# DC-Motor-DRV.net
KiCad netlist of a schematic drawn in Altium Designer
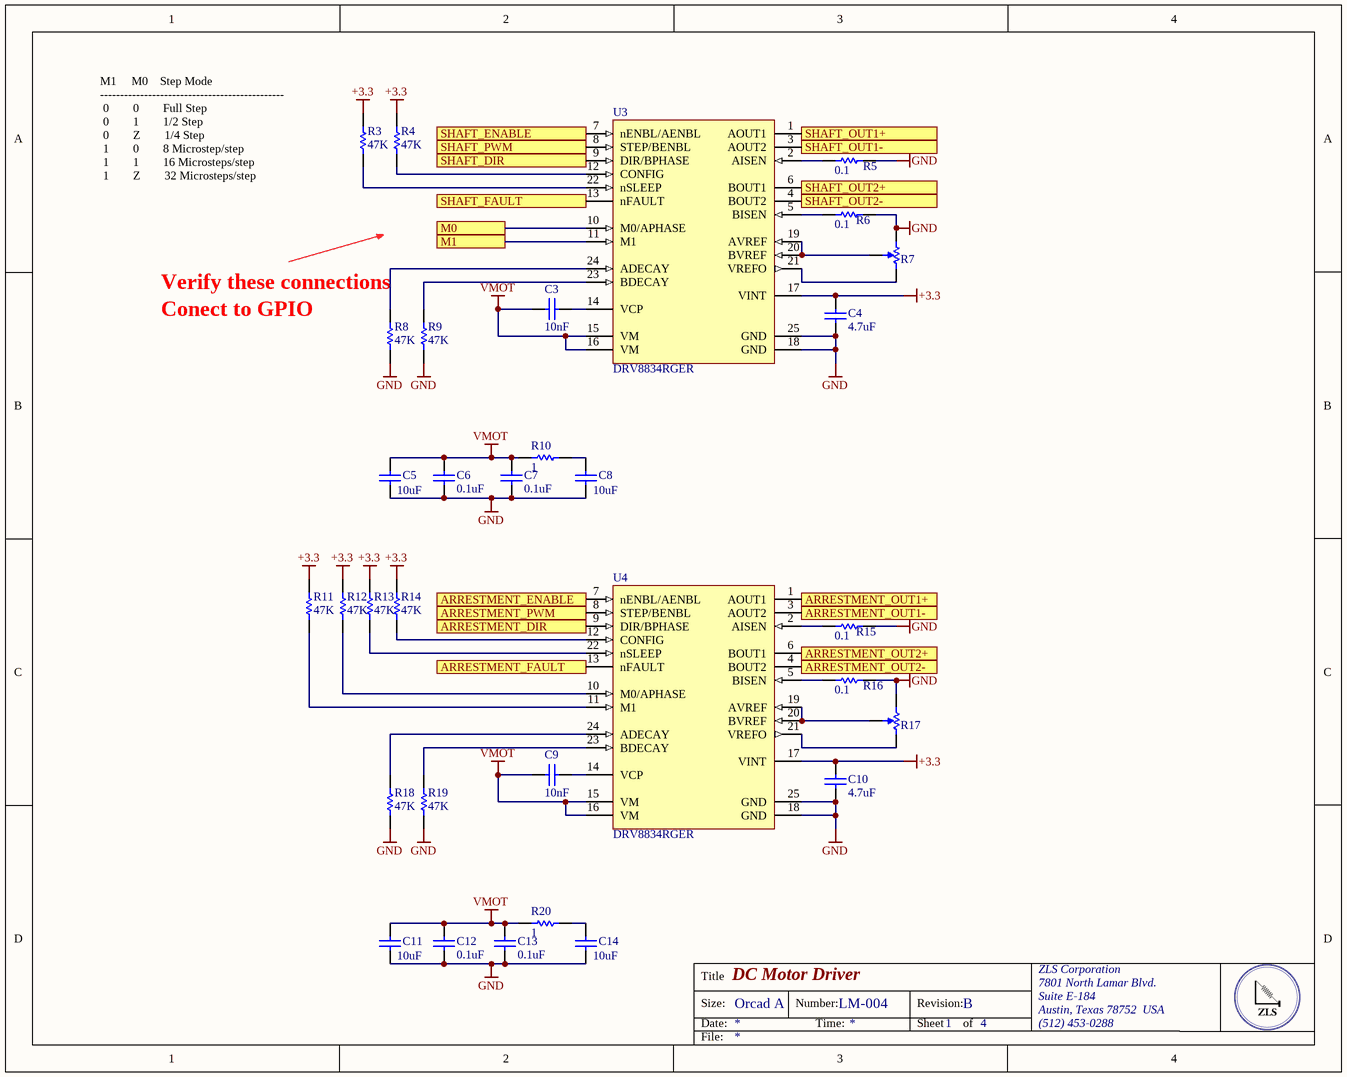
[diagram p0: DC-Motor-DRV.SchDoc]

(export (version "E")
  (design (tool "Eeschema 10.0.6"))
  (components
    (comp (ref "C3")
      (value "10nF")
      (footprint "CAPC0603(1608)100_L")
      (description "CAP 10nF 16V ±20% 0603 (1608 Metric) Thickness 1mm SMD")
      (fields (field (name "TOLERANCE") "Â±20%") (field (name "MANUFACTURER") "Kyocera AVX"))
      (libsource (lib "Altium Content Vault") (part "CAP"))
    )
    (comp (ref "C4")
      (value "4.7uF")
      (footprint "CAPC0603(1608)55_M")
      (description "CAP 4.7uF 6.3V ±10% 0603 (1608 Metric) Thickness 0.55mm SMD")
      (fields (field (name "TOLERANCE") "Â±10%") (field (name "MANUFACTURER") "KEMET"))
      (libsource (lib "Altium Content Vault") (part "CAP"))
    )
    (comp (ref "C5")
      (value "10uF")
      (footprint "CAPC0805(2012)145_N")
      (description "CAP CER 0.1UF 25V X7R 0805")
      (fields
        (field (name "MANUFACTURER") "Murata Electronics North America")
        (field (name "MANUFACTURER PART NUMBER") "GRM21BR71E104KA01L")
      )
      (libsource (lib "Altium Content Vault") (part "CMP-1036-04795-1"))
    )
    (comp (ref "C6")
      (value "0.1uF")
      (footprint "CAPC1608X94X35LL15T15")
      (description "CAP .1UF 16V CERAMIC X7R 0603")
      (fields
        (field (name "MANUFACTURER") "Yageo")
        (field (name "MANUFACTURER PART NUMBER") "CC0603KRX7R7BB105")
      )
      (libsource (lib "Altium Content Vault") (part "CAP-NP-2"))
    )
    (comp (ref "C7")
      (value "0.1uF")
      (footprint "CAPC1608X94X35LL15T15")
      (description "CAP .1UF 16V CERAMIC X7R 0603")
      (fields
        (field (name "MANUFACTURER") "Yageo")
        (field (name "MANUFACTURER PART NUMBER") "CC0603KRX7R7BB105")
      )
      (libsource (lib "Altium Content Vault") (part "CAP-NP-2"))
    )
    (comp (ref "C8")
      (value "10uF")
      (footprint "CAPC0805(2012)145_N")
      (description "CAP CER 0.1UF 25V X7R 0805")
      (fields
        (field (name "MANUFACTURER") "Murata Electronics North America")
        (field (name "MANUFACTURER PART NUMBER") "GRM21BR71E104KA01L")
      )
      (libsource (lib "Altium Content Vault") (part "CMP-1036-04795-1"))
    )
    (comp (ref "C9")
      (value "10nF")
      (footprint "CAPC0603(1608)100_L")
      (description "CAP 10nF 16V ±20% 0603 (1608 Metric) Thickness 1mm SMD")
      (fields (field (name "TOLERANCE") "Â±20%") (field (name "MANUFACTURER") "Kyocera AVX"))
      (libsource (lib "Altium Content Vault") (part "CAP"))
    )
    (comp (ref "C10")
      (value "4.7uF")
      (footprint "CAPC0603(1608)55_M")
      (description "CAP 4.7uF 6.3V ±10% 0603 (1608 Metric) Thickness 0.55mm SMD")
      (fields (field (name "TOLERANCE") "Â±10%") (field (name "MANUFACTURER") "KEMET"))
      (libsource (lib "Altium Content Vault") (part "CAP"))
    )
    (comp (ref "C11")
      (value "10uF")
      (footprint "CAPC0805(2012)145_N")
      (description "CAP CER 0.1UF 25V X7R 0805")
      (fields
        (field (name "MANUFACTURER") "Murata Electronics North America")
        (field (name "MANUFACTURER PART NUMBER") "GRM21BR71E104KA01L")
      )
      (libsource (lib "Altium Content Vault") (part "CMP-1036-04795-1"))
    )
    (comp (ref "C12")
      (value "0.1uF")
      (footprint "CAPC1608X94X35LL15T15")
      (description "CAP .1UF 16V CERAMIC X7R 0603")
      (fields
        (field (name "MANUFACTURER") "Yageo")
        (field (name "MANUFACTURER PART NUMBER") "CC0603KRX7R7BB105")
      )
      (libsource (lib "Altium Content Vault") (part "CAP-NP-2"))
    )
    (comp (ref "C13")
      (value "0.1uF")
      (footprint "CAPC1608X94X35LL15T15")
      (description "CAP .1UF 16V CERAMIC X7R 0603")
      (fields
        (field (name "MANUFACTURER") "Yageo")
        (field (name "MANUFACTURER PART NUMBER") "CC0603KRX7R7BB105")
      )
      (libsource (lib "Altium Content Vault") (part "CAP-NP-2"))
    )
    (comp (ref "C14")
      (value "10uF")
      (footprint "CAPC0805(2012)145_N")
      (description "CAP CER 0.1UF 25V X7R 0805")
      (fields
        (field (name "MANUFACTURER") "Murata Electronics North America")
        (field (name "MANUFACTURER PART NUMBER") "GRM21BR71E104KA01L")
      )
      (libsource (lib "Altium Content Vault") (part "CMP-1036-04795-1"))
    )
    (comp (ref "R3")
      (value "47K")
      (footprint "RESC0603(1608)_N")
      (description "RES SMD 10K OHM 1% 1/10W 0603")
      (fields
        (field (name "MANUFACTURER") "Vishay")
        (field (name "MANUFACTURER PART NUMBER") "CRCW060310K0FKEA")
      )
      (libsource (lib "Altium Content Vault") (part "RES"))
    )
    (comp (ref "R4")
      (value "47K")
      (footprint "RESC0603(1608)_N")
      (description "RES SMD 10K OHM 1% 1/10W 0603")
      (fields
        (field (name "MANUFACTURER") "Vishay")
        (field (name "MANUFACTURER PART NUMBER") "CRCW060310K0FKEA")
      )
      (libsource (lib "Altium Content Vault") (part "RES"))
    )
    (comp (ref "R5")
      (value "0.1")
      (footprint "RESC0603(1608)_N")
      (description "0R12 0.1W 1% 0603 (1608 Metric)  SMD")
      (fields (field (name "POWER") "0.1 W") (field (name "TOLERANCE") "1 %"))
      (libsource (lib "Altium Content Vault") (part "RES"))
    )
    (comp (ref "R6")
      (value "0.1")
      (footprint "RESC0603(1608)_N")
      (description "0R12 0.1W 1% 0603 (1608 Metric)  SMD")
      (fields (field (name "POWER") "0.1 W") (field (name "TOLERANCE") "1 %"))
      (libsource (lib "Altium Content Vault") (part "RES"))
    )
    (comp (ref "R7")
      (value "3313J-1-503E")
      (footprint "BOUR-3313J-1_V")
      (fields (field (name "MANUFACTURER") "Bourns"))
      (libsource (lib "Altium Content Vault") (part "CMP-2000-05588-1"))
    )
    (comp (ref "R8")
      (value "47K")
      (footprint "RESC0603(1608)_N")
      (description "RES SMD 10K OHM 1% 1/10W 0603")
      (fields
        (field (name "MANUFACTURER") "Vishay")
        (field (name "MANUFACTURER PART NUMBER") "CRCW060310K0FKEA")
      )
      (libsource (lib "Altium Content Vault") (part "RES"))
    )
    (comp (ref "R9")
      (value "47K")
      (footprint "RESC0603(1608)_N")
      (description "RES SMD 10K OHM 1% 1/10W 0603")
      (fields
        (field (name "MANUFACTURER") "Vishay")
        (field (name "MANUFACTURER PART NUMBER") "CRCW060310K0FKEA")
      )
      (libsource (lib "Altium Content Vault") (part "RES"))
    )
    (comp (ref "R10")
      (value "1")
      (footprint "RESC0603(1608)_N")
      (description "RES SMD 1 OHM 1% 1/10W 0603")
      (fields
        (field (name "MANUFACTURER") "Vishay Dale")
        (field (name "MANUFACTURER PART NUMBER") "CRCW06031R00FKEA")
      )
      (libsource (lib "Altium Content Vault") (part "RES"))
    )
    (comp (ref "R11")
      (value "47K")
      (footprint "RESC0603(1608)_N")
      (description "RES SMD 10K OHM 1% 1/10W 0603")
      (fields
        (field (name "MANUFACTURER") "Vishay")
        (field (name "MANUFACTURER PART NUMBER") "CRCW060310K0FKEA")
      )
      (libsource (lib "Altium Content Vault") (part "RES"))
    )
    (comp (ref "R12")
      (value "47K")
      (footprint "RESC0603(1608)_N")
      (description "RES SMD 10K OHM 1% 1/10W 0603")
      (fields
        (field (name "MANUFACTURER") "Vishay")
        (field (name "MANUFACTURER PART NUMBER") "CRCW060310K0FKEA")
      )
      (libsource (lib "Altium Content Vault") (part "RES"))
    )
    (comp (ref "R13")
      (value "47K")
      (footprint "RESC0603(1608)_N")
      (description "RES SMD 10K OHM 1% 1/10W 0603")
      (fields
        (field (name "MANUFACTURER") "Vishay")
        (field (name "MANUFACTURER PART NUMBER") "CRCW060310K0FKEA")
      )
      (libsource (lib "Altium Content Vault") (part "RES"))
    )
    (comp (ref "R14")
      (value "47K")
      (footprint "RESC0603(1608)_N")
      (description "RES SMD 10K OHM 1% 1/10W 0603")
      (fields
        (field (name "MANUFACTURER") "Vishay")
        (field (name "MANUFACTURER PART NUMBER") "CRCW060310K0FKEA")
      )
      (libsource (lib "Altium Content Vault") (part "RES"))
    )
    (comp (ref "R15")
      (value "0.1")
      (footprint "RESC0603(1608)_N")
      (description "0R12 0.1W 1% 0603 (1608 Metric)  SMD")
      (fields (field (name "POWER") "0.1 W") (field (name "TOLERANCE") "1 %"))
      (libsource (lib "Altium Content Vault") (part "RES"))
    )
    (comp (ref "R16")
      (value "0.1")
      (footprint "RESC0603(1608)_N")
      (description "0R12 0.1W 1% 0603 (1608 Metric)  SMD")
      (fields (field (name "POWER") "0.1 W") (field (name "TOLERANCE") "1 %"))
      (libsource (lib "Altium Content Vault") (part "RES"))
    )
    (comp (ref "R17")
      (value "3313J-1-503E")
      (footprint "BOUR-3313J-1_V")
      (fields (field (name "MANUFACTURER") "Bourns"))
      (libsource (lib "Altium Content Vault") (part "CMP-2000-05588-1"))
    )
    (comp (ref "R18")
      (value "47K")
      (footprint "RESC0603(1608)_N")
      (description "RES SMD 10K OHM 1% 1/10W 0603")
      (fields
        (field (name "MANUFACTURER") "Vishay")
        (field (name "MANUFACTURER PART NUMBER") "CRCW060310K0FKEA")
      )
      (libsource (lib "Altium Content Vault") (part "RES"))
    )
    (comp (ref "R19")
      (value "47K")
      (footprint "RESC0603(1608)_N")
      (description "RES SMD 10K OHM 1% 1/10W 0603")
      (fields
        (field (name "MANUFACTURER") "Vishay")
        (field (name "MANUFACTURER PART NUMBER") "CRCW060310K0FKEA")
      )
      (libsource (lib "Altium Content Vault") (part "RES"))
    )
    (comp (ref "R20")
      (value "1")
      (footprint "RESC0603(1608)_N")
      (description "RES SMD 1 OHM 1% 1/10W 0603")
      (fields
        (field (name "MANUFACTURER") "Vishay Dale")
        (field (name "MANUFACTURER PART NUMBER") "CRCW06031R00FKEA")
      )
      (libsource (lib "Altium Content Vault") (part "RES"))
    )
    (comp (ref "U3")
      (value "DRV8834RGER")
      (footprint "RGE0024B_V")
      (libsource (lib "Altium Content Vault") (part "TI-DRV8834RGE-24"))
    )
    (comp (ref "U4")
      (value "DRV8834RGER")
      (footprint "RGE0024B_V")
      (libsource (lib "Altium Content Vault") (part "TI-DRV8834RGE-24"))
    )
  )
  (nets
    (net (code "1") (name "+3.3") (class "Default")
      (node (ref "C10") (pin "2") (pinfunction "2_2") (pintype "passive"))
      (node (ref "C4") (pin "2") (pinfunction "2_2") (pintype "passive"))
      (node (ref "R11") (pin "2") (pinfunction "2_2") (pintype "passive"))
      (node (ref "R12") (pin "2") (pinfunction "2_2") (pintype "passive"))
      (node (ref "R13") (pin "2") (pinfunction "2_2") (pintype "passive"))
      (node (ref "R14") (pin "2") (pinfunction "2_2") (pintype "passive"))
      (node (ref "R3") (pin "2") (pinfunction "2_2") (pintype "passive"))
      (node (ref "R4") (pin "2") (pinfunction "2_2") (pintype "passive"))
      (node (ref "U3") (pin "17") (pinfunction "VINT_17") (pintype "passive"))
      (node (ref "U4") (pin "17") (pinfunction "VINT_17") (pintype "passive"))
    )
    (net (code "2") (name "/ARRESTMENT_DIR") (class "Default")
      (node (ref "U4") (pin "9") (pinfunction "DIR/BPHASE_9") (pintype "input"))
    )
    (net (code "3") (name "/ARRESTMENT_ENABLE") (class "Default")
      (node (ref "U4") (pin "7") (pinfunction "nENBL/AENBL_7") (pintype "input"))
    )
    (net (code "4") (name "/ARRESTMENT_FAULT") (class "Default")
      (node (ref "U4") (pin "13") (pinfunction "nFAULT_13") (pintype "open_collector"))
    )
    (net (code "5") (name "/ARRESTMENT_OUT1+") (class "Default")
      (node (ref "U4") (pin "1") (pinfunction "AOUT1_1") (pintype "tri_state"))
    )
    (net (code "6") (name "/ARRESTMENT_OUT1-") (class "Default")
      (node (ref "U4") (pin "3") (pinfunction "AOUT2_3") (pintype "tri_state"))
    )
    (net (code "7") (name "/ARRESTMENT_OUT2+") (class "Default")
      (node (ref "U4") (pin "6") (pinfunction "BOUT1_6") (pintype "tri_state"))
    )
    (net (code "8") (name "/ARRESTMENT_OUT2-") (class "Default")
      (node (ref "U4") (pin "4") (pinfunction "BOUT2_4") (pintype "tri_state"))
    )
    (net (code "9") (name "/ARRESTMENT_PWM") (class "Default")
      (node (ref "U4") (pin "8") (pinfunction "STEP/BENBL_8") (pintype "input"))
    )
    (net (code "10") (name "/M0") (class "Default")
      (node (ref "U3") (pin "10") (pinfunction "M0/APHASE_10") (pintype "input"))
    )
    (net (code "11") (name "/M1") (class "Default")
      (node (ref "U3") (pin "11") (pinfunction "M1_11") (pintype "input"))
    )
    (net (code "12") (name "/SHAFT_DIR") (class "Default")
      (node (ref "U3") (pin "9") (pinfunction "DIR/BPHASE_9") (pintype "input"))
    )
    (net (code "13") (name "/SHAFT_ENABLE") (class "Default")
      (node (ref "U3") (pin "7") (pinfunction "nENBL/AENBL_7") (pintype "input"))
    )
    (net (code "14") (name "/SHAFT_FAULT") (class "Default")
      (node (ref "U3") (pin "13") (pinfunction "nFAULT_13") (pintype "open_collector"))
    )
    (net (code "15") (name "/SHAFT_OUT1+") (class "Default")
      (node (ref "U3") (pin "1") (pinfunction "AOUT1_1") (pintype "tri_state"))
    )
    (net (code "16") (name "/SHAFT_OUT1-") (class "Default")
      (node (ref "U3") (pin "3") (pinfunction "AOUT2_3") (pintype "tri_state"))
    )
    (net (code "17") (name "/SHAFT_OUT2+") (class "Default")
      (node (ref "U3") (pin "6") (pinfunction "BOUT1_6") (pintype "tri_state"))
    )
    (net (code "18") (name "/SHAFT_OUT2-") (class "Default")
      (node (ref "U3") (pin "4") (pinfunction "BOUT2_4") (pintype "tri_state"))
    )
    (net (code "19") (name "/SHAFT_PWM") (class "Default")
      (node (ref "U3") (pin "8") (pinfunction "STEP/BENBL_8") (pintype "input"))
    )
    (net (code "20") (name "GND") (class "Default")
      (node (ref "C10") (pin "1") (pinfunction "1_1") (pintype "passive"))
      (node (ref "C11") (pin "1") (pinfunction "1_1") (pintype "passive"))
      (node (ref "C12") (pin "2") (pinfunction "2_2") (pintype "passive"))
      (node (ref "C13") (pin "2") (pinfunction "2_2") (pintype "passive"))
      (node (ref "C14") (pin "1") (pinfunction "1_1") (pintype "passive"))
      (node (ref "C4") (pin "1") (pinfunction "1_1") (pintype "passive"))
      (node (ref "C5") (pin "1") (pinfunction "1_1") (pintype "passive"))
      (node (ref "C6") (pin "2") (pinfunction "2_2") (pintype "passive"))
      (node (ref "C7") (pin "2") (pinfunction "2_2") (pintype "passive"))
      (node (ref "C8") (pin "1") (pinfunction "1_1") (pintype "passive"))
      (node (ref "R15") (pin "2") (pinfunction "2_2") (pintype "passive"))
      (node (ref "R16") (pin "2") (pinfunction "2_2") (pintype "passive"))
      (node (ref "R17") (pin "1") (pinfunction "1_1") (pintype "passive"))
      (node (ref "R18") (pin "1") (pinfunction "1_1") (pintype "passive"))
      (node (ref "R19") (pin "1") (pinfunction "1_1") (pintype "passive"))
      (node (ref "R5") (pin "2") (pinfunction "2_2") (pintype "passive"))
      (node (ref "R6") (pin "2") (pinfunction "2_2") (pintype "passive"))
      (node (ref "R7") (pin "1") (pinfunction "1_1") (pintype "passive"))
      (node (ref "R8") (pin "1") (pinfunction "1_1") (pintype "passive"))
      (node (ref "R9") (pin "1") (pinfunction "1_1") (pintype "passive"))
      (node (ref "U3") (pin "18") (pinfunction "GND_18") (pintype "power_in"))
      (node (ref "U3") (pin "25") (pinfunction "GND_25") (pintype "power_in"))
      (node (ref "U4") (pin "18") (pinfunction "GND_18") (pintype "power_in"))
      (node (ref "U4") (pin "25") (pinfunction "GND_25") (pintype "power_in"))
    )
    (net (code "21") (name "Net-(C8-Pad2)") (class "Default")
      (node (ref "C8") (pin "2") (pinfunction "2_2") (pintype "passive"))
      (node (ref "R10") (pin "1") (pinfunction "1_1") (pintype "passive"))
    )
    (net (code "22") (name "Net-(C14-Pad2)") (class "Default")
      (node (ref "C14") (pin "2") (pinfunction "2_2") (pintype "passive"))
      (node (ref "R20") (pin "1") (pinfunction "1_1") (pintype "passive"))
    )
    (net (code "23") (name "Net-(U3-ADECAY)") (class "Default")
      (node (ref "R8") (pin "2") (pinfunction "2_2") (pintype "passive"))
      (node (ref "U3") (pin "24") (pinfunction "ADECAY_24") (pintype "input"))
    )
    (net (code "24") (name "Net-(U3-AISEN)") (class "Default")
      (node (ref "R5") (pin "1") (pinfunction "1_1") (pintype "passive"))
      (node (ref "U3") (pin "2") (pinfunction "AISEN_2") (pintype "input"))
    )
    (net (code "25") (name "Net-(U3-AVREF)") (class "Default")
      (node (ref "R7") (pin "2") (pinfunction "2_2") (pintype "passive"))
      (node (ref "U3") (pin "19") (pinfunction "AVREF_19") (pintype "input"))
      (node (ref "U3") (pin "20") (pinfunction "BVREF_20") (pintype "input"))
    )
    (net (code "26") (name "Net-(U3-BDECAY)") (class "Default")
      (node (ref "R9") (pin "2") (pinfunction "2_2") (pintype "passive"))
      (node (ref "U3") (pin "23") (pinfunction "BDECAY_23") (pintype "input"))
    )
    (net (code "27") (name "Net-(U3-BISEN)") (class "Default")
      (node (ref "R6") (pin "1") (pinfunction "1_1") (pintype "passive"))
      (node (ref "U3") (pin "5") (pinfunction "BISEN_5") (pintype "input"))
    )
    (net (code "28") (name "Net-(U3-CONFIG)") (class "Default")
      (node (ref "R4") (pin "1") (pinfunction "1_1") (pintype "passive"))
      (node (ref "U3") (pin "12") (pinfunction "CONFIG_12") (pintype "input"))
    )
    (net (code "29") (name "Net-(U3-VCP)") (class "Default")
      (node (ref "C3") (pin "2") (pinfunction "2_2") (pintype "passive"))
      (node (ref "U3") (pin "14") (pinfunction "VCP_14") (pintype "passive"))
    )
    (net (code "30") (name "Net-(U3-VREFO)") (class "Default")
      (node (ref "R7") (pin "3") (pinfunction "3_3") (pintype "passive"))
      (node (ref "U3") (pin "21") (pinfunction "VREFO_21") (pintype "output"))
    )
    (net (code "31") (name "Net-(U3-nSLEEP)") (class "Default")
      (node (ref "R3") (pin "1") (pinfunction "1_1") (pintype "passive"))
      (node (ref "U3") (pin "22") (pinfunction "nSLEEP_22") (pintype "input"))
    )
    (net (code "32") (name "Net-(U4-ADECAY)") (class "Default")
      (node (ref "R18") (pin "2") (pinfunction "2_2") (pintype "passive"))
      (node (ref "U4") (pin "24") (pinfunction "ADECAY_24") (pintype "input"))
    )
    (net (code "33") (name "Net-(U4-AISEN)") (class "Default")
      (node (ref "R15") (pin "1") (pinfunction "1_1") (pintype "passive"))
      (node (ref "U4") (pin "2") (pinfunction "AISEN_2") (pintype "input"))
    )
    (net (code "34") (name "Net-(U4-AVREF)") (class "Default")
      (node (ref "R17") (pin "2") (pinfunction "2_2") (pintype "passive"))
      (node (ref "U4") (pin "19") (pinfunction "AVREF_19") (pintype "input"))
      (node (ref "U4") (pin "20") (pinfunction "BVREF_20") (pintype "input"))
    )
    (net (code "35") (name "Net-(U4-BDECAY)") (class "Default")
      (node (ref "R19") (pin "2") (pinfunction "2_2") (pintype "passive"))
      (node (ref "U4") (pin "23") (pinfunction "BDECAY_23") (pintype "input"))
    )
    (net (code "36") (name "Net-(U4-BISEN)") (class "Default")
      (node (ref "R16") (pin "1") (pinfunction "1_1") (pintype "passive"))
      (node (ref "U4") (pin "5") (pinfunction "BISEN_5") (pintype "input"))
    )
    (net (code "37") (name "Net-(U4-CONFIG)") (class "Default")
      (node (ref "R14") (pin "1") (pinfunction "1_1") (pintype "passive"))
      (node (ref "U4") (pin "12") (pinfunction "CONFIG_12") (pintype "input"))
    )
    (net (code "38") (name "Net-(U4-M0{slash}APHASE)") (class "Default")
      (node (ref "R12") (pin "1") (pinfunction "1_1") (pintype "passive"))
      (node (ref "U4") (pin "10") (pinfunction "M0/APHASE_10") (pintype "input"))
    )
    (net (code "39") (name "Net-(U4-M1)") (class "Default")
      (node (ref "R11") (pin "1") (pinfunction "1_1") (pintype "passive"))
      (node (ref "U4") (pin "11") (pinfunction "M1_11") (pintype "input"))
    )
    (net (code "40") (name "Net-(U4-VCP)") (class "Default")
      (node (ref "C9") (pin "2") (pinfunction "2_2") (pintype "passive"))
      (node (ref "U4") (pin "14") (pinfunction "VCP_14") (pintype "passive"))
    )
    (net (code "41") (name "Net-(U4-VREFO)") (class "Default")
      (node (ref "R17") (pin "3") (pinfunction "3_3") (pintype "passive"))
      (node (ref "U4") (pin "21") (pinfunction "VREFO_21") (pintype "output"))
    )
    (net (code "42") (name "Net-(U4-nSLEEP)") (class "Default")
      (node (ref "R13") (pin "1") (pinfunction "1_1") (pintype "passive"))
      (node (ref "U4") (pin "22") (pinfunction "nSLEEP_22") (pintype "input"))
    )
    (net (code "43") (name "VMOT") (class "Default")
      (node (ref "C11") (pin "2") (pinfunction "2_2") (pintype "passive"))
      (node (ref "C12") (pin "1") (pinfunction "1_1") (pintype "passive"))
      (node (ref "C13") (pin "1") (pinfunction "1_1") (pintype "passive"))
      (node (ref "C3") (pin "1") (pinfunction "1_1") (pintype "passive"))
      (node (ref "C5") (pin "2") (pinfunction "2_2") (pintype "passive"))
      (node (ref "C6") (pin "1") (pinfunction "1_1") (pintype "passive"))
      (node (ref "C7") (pin "1") (pinfunction "1_1") (pintype "passive"))
      (node (ref "C9") (pin "1") (pinfunction "1_1") (pintype "passive"))
      (node (ref "R10") (pin "2") (pinfunction "2_2") (pintype "passive"))
      (node (ref "R20") (pin "2") (pinfunction "2_2") (pintype "passive"))
      (node (ref "U3") (pin "15") (pinfunction "VM_15") (pintype "power_in"))
      (node (ref "U3") (pin "16") (pinfunction "VM_16") (pintype "power_in"))
      (node (ref "U4") (pin "15") (pinfunction "VM_15") (pintype "power_in"))
      (node (ref "U4") (pin "16") (pinfunction "VM_16") (pintype "power_in"))
    )
  )
)
